# page1.net
KiCad netlist of a schematic drawn in EAGLE
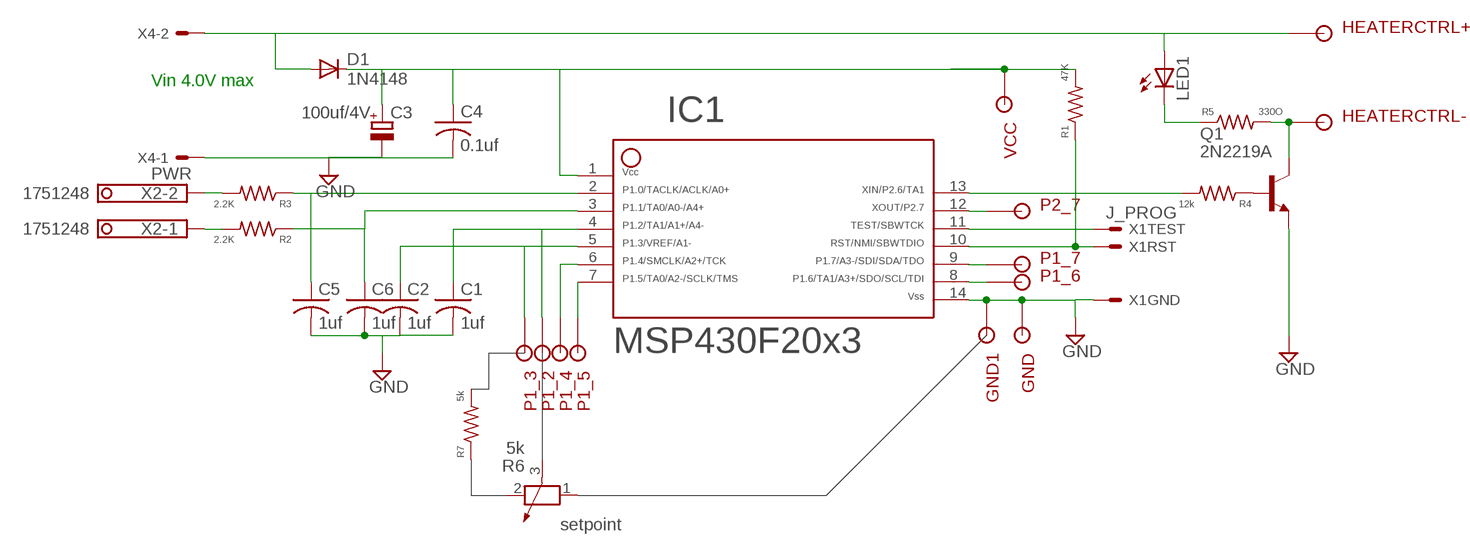
[diagram p0: schematic, sheet 1]

(export (version "E")
  (design (tool "Eeschema 10.0.6"))
  (components
    (comp (ref "C1")
      (value "1uf")
      (footprint "eagle-import:C0805")
      (libsource (lib "eagle-import") (part "C-USC0805"))
    )
    (comp (ref "C2")
      (value "1uf")
      (footprint "eagle-import:C0805")
      (libsource (lib "eagle-import") (part "C-USC0805"))
    )
    (comp (ref "C3")
      (value "100uf/4V")
      (footprint "eagle-import:SMC_B")
      (libsource (lib "eagle-import") (part "CPOL-EUSMCB"))
    )
    (comp (ref "C4")
      (value "0.1uf")
      (footprint "eagle-import:C0805")
      (libsource (lib "eagle-import") (part "C-USC0805"))
    )
    (comp (ref "C5")
      (value "1uf")
      (footprint "eagle-import:C0805")
      (libsource (lib "eagle-import") (part "C-USC0805"))
    )
    (comp (ref "C6")
      (value "1uf")
      (footprint "eagle-import:C0805")
      (libsource (lib "eagle-import") (part "C-USC0805"))
    )
    (comp (ref "D1")
      (value "1N4148")
      (footprint "eagle-import:DIO-35-10")
      (libsource (lib "eagle-import") (part "1N4148"))
    )
    (comp (ref "GND")
      (value "SOLDER_POINTA")
      (footprint "eagle-import:P1-13")
      (libsource (lib "eagle-import") (part "SOLDER_POINTA"))
    )
    (comp (ref "GND1")
      (value "SOLDER_POINTA")
      (footprint "eagle-import:P1-13")
      (libsource (lib "eagle-import") (part "SOLDER_POINTA"))
    )
    (comp (ref "HEATERCTRL+")
      (value "SOLDER_POINTA")
      (footprint "eagle-import:P1-13")
      (libsource (lib "eagle-import") (part "SOLDER_POINTA"))
    )
    (comp (ref "HEATERCTRL-")
      (value "SOLDER_POINTA")
      (footprint "eagle-import:P1-13")
      (libsource (lib "eagle-import") (part "SOLDER_POINTA"))
    )
    (comp (ref "IC1")
      (value "F20X3---N14")
      (footprint "eagle-import:N14")
      (libsource (lib "eagle-import") (part "F20X3---N14"))
    )
    (comp (ref "LED1")
      (value "LED5MM")
      (footprint "eagle-import:LED5MM")
      (libsource (lib "eagle-import") (part "LED5MM"))
    )
    (comp (ref "P1_2")
      (value "SOLDER_POINTA")
      (footprint "eagle-import:P1-13")
      (libsource (lib "eagle-import") (part "SOLDER_POINTA"))
    )
    (comp (ref "P1_3")
      (value "SOLDER_POINTA")
      (footprint "eagle-import:P1-13")
      (libsource (lib "eagle-import") (part "SOLDER_POINTA"))
    )
    (comp (ref "P1_4")
      (value "SOLDER_POINTA")
      (footprint "eagle-import:P1-13")
      (libsource (lib "eagle-import") (part "SOLDER_POINTA"))
    )
    (comp (ref "P1_5")
      (value "SOLDER_POINTA")
      (footprint "eagle-import:P1-13")
      (libsource (lib "eagle-import") (part "SOLDER_POINTA"))
    )
    (comp (ref "P1_6")
      (value "SOLDER_POINTA")
      (footprint "eagle-import:P1-13")
      (libsource (lib "eagle-import") (part "SOLDER_POINTA"))
    )
    (comp (ref "P1_7")
      (value "SOLDER_POINTA")
      (footprint "eagle-import:P1-13")
      (libsource (lib "eagle-import") (part "SOLDER_POINTA"))
    )
    (comp (ref "P2_7")
      (value "SOLDER_POINTA")
      (footprint "eagle-import:P1-13")
      (libsource (lib "eagle-import") (part "SOLDER_POINTA"))
    )
    (comp (ref "Q1")
      (value "2N2219A")
      (footprint "eagle-import:TO92-EBC")
      (libsource (lib "eagle-import") (part "2N2219ATO92_EBC"))
    )
    (comp (ref "R1")
      (value "47K")
      (footprint "eagle-import:M0805")
      (libsource (lib "eagle-import") (part "R-US_M0805"))
    )
    (comp (ref "R2")
      (value "2.2K")
      (footprint "eagle-import:M0805")
      (libsource (lib "eagle-import") (part "R-US_M0805"))
    )
    (comp (ref "R3")
      (value "2.2K")
      (footprint "eagle-import:M0805")
      (libsource (lib "eagle-import") (part "R-US_M0805"))
    )
    (comp (ref "R4")
      (value "12k")
      (footprint "eagle-import:M0805")
      (libsource (lib "eagle-import") (part "R-US_M0805"))
    )
    (comp (ref "R5")
      (value "330O")
      (footprint "eagle-import:0207_15")
      (libsource (lib "eagle-import") (part "R-US_0207/15"))
    )
    (comp (ref "R6")
      (value "5k")
      (footprint "eagle-import:PT-10")
      (libsource (lib "eagle-import") (part "POTENTIOMETER_PT-10"))
    )
    (comp (ref "R7")
      (value "5k")
      (footprint "eagle-import:0207_15")
      (libsource (lib "eagle-import") (part "R-US_0207/15"))
    )
    (comp (ref "VCC")
      (value "SOLDER_POINTA")
      (footprint "eagle-import:P1-13")
      (libsource (lib "eagle-import") (part "SOLDER_POINTA"))
    )
    (comp (ref "X1")
      (value "J_PROG")
      (footprint "eagle-import:MOLEX-3PIN")
      (libsource (lib "eagle-import") (part "J_PROG_MSP430"))
    )
    (comp (ref "X2")
      (value "1751248")
      (footprint "eagle-import:1751248")
      (libsource (lib "eagle-import") (part "1751248"))
    )
    (comp (ref "X4")
      (value "PWR")
      (footprint "eagle-import:22-23-2021")
      (libsource (lib "eagle-import") (part "22-23-2021"))
    )
  )
  (nets
    (net (code "1") (name "GND") (class "Default")
      (node (ref "C1") (pin "2") (pinfunction "2_2") (pintype "passive"))
      (node (ref "C2") (pin "2") (pinfunction "2_2") (pintype "passive"))
      (node (ref "C3") (pin "-") (pinfunction "-_-") (pintype "passive"))
      (node (ref "C4") (pin "2") (pinfunction "2_2") (pintype "passive"))
      (node (ref "C5") (pin "2") (pinfunction "2_2") (pintype "passive"))
      (node (ref "C6") (pin "2") (pinfunction "2_2") (pintype "passive"))
      (node (ref "GND") (pin "1") (pinfunction "P$1_1") (pintype "bidirectional"))
      (node (ref "GND1") (pin "1") (pinfunction "P$1_1") (pintype "bidirectional"))
      (node (ref "IC1") (pin "14") (pinfunction "14_14") (pintype "power_in"))
      (node (ref "Q1") (pin "E") (pinfunction "E_E") (pintype "passive"))
      (node (ref "X1") (pin "3") (pinfunction "S_3") (pintype "passive"))
      (node (ref "X4") (pin "1") (pinfunction "S_1") (pintype "passive"))
    )
    (net (code "2") (name "Net-(C5-Pad1)") (class "Default")
      (node (ref "C5") (pin "1") (pinfunction "1_1") (pintype "passive"))
      (node (ref "IC1") (pin "2") (pinfunction "2_2") (pintype "bidirectional"))
      (node (ref "R3") (pin "1") (pinfunction "1_1") (pintype "passive"))
    )
    (net (code "3") (name "Net-(C6-Pad1)") (class "Default")
      (node (ref "C6") (pin "1") (pinfunction "1_1") (pintype "passive"))
      (node (ref "IC1") (pin "3") (pinfunction "3_3") (pintype "bidirectional"))
      (node (ref "R2") (pin "1") (pinfunction "1_1") (pintype "passive"))
    )
    (net (code "4") (name "Net-(D1-A)") (class "Default")
      (node (ref "D1") (pin "P$2") (pinfunction "A_P$2") (pintype "passive"))
      (node (ref "HEATERCTRL+") (pin "1") (pinfunction "P$1_1") (pintype "bidirectional"))
      (node (ref "LED1") (pin "A") (pinfunction "A_A") (pintype "passive"))
      (node (ref "X4") (pin "2") (pinfunction "S_2") (pintype "passive"))
    )
    (net (code "5") (name "Net-(D1-C)") (class "Default")
      (node (ref "C3") (pin "+") (pinfunction "+_+") (pintype "passive"))
      (node (ref "C4") (pin "1") (pinfunction "1_1") (pintype "passive"))
      (node (ref "D1") (pin "P$1") (pinfunction "C_P$1") (pintype "passive"))
      (node (ref "IC1") (pin "1") (pinfunction "1_1") (pintype "power_in"))
      (node (ref "R1") (pin "2") (pinfunction "2_2") (pintype "passive"))
      (node (ref "VCC") (pin "1") (pinfunction "P$1_1") (pintype "bidirectional"))
    )
    (net (code "6") (name "Net-(HEATERCTRL--P$1)") (class "Default")
      (node (ref "HEATERCTRL-") (pin "1") (pinfunction "P$1_1") (pintype "bidirectional"))
      (node (ref "Q1") (pin "C") (pinfunction "C_C") (pintype "passive"))
      (node (ref "R5") (pin "2") (pinfunction "2_2") (pintype "passive"))
    )
    (net (code "7") (name "Net-(IC1-Pad13)") (class "Default")
      (node (ref "IC1") (pin "13") (pinfunction "13_13") (pintype "bidirectional"))
      (node (ref "R4") (pin "2") (pinfunction "2_2") (pintype "passive"))
    )
    (net (code "8") (name "Net-(LED1-C)") (class "Default")
      (node (ref "LED1") (pin "K") (pinfunction "C_K") (pintype "passive"))
      (node (ref "R5") (pin "1") (pinfunction "1_1") (pintype "passive"))
    )
    (net (code "9") (name "Net-(P1_2-P$1)") (class "Default")
      (node (ref "C1") (pin "1") (pinfunction "1_1") (pintype "passive"))
      (node (ref "IC1") (pin "4") (pinfunction "4_4") (pintype "bidirectional"))
      (node (ref "P1_2") (pin "1") (pinfunction "P$1_1") (pintype "bidirectional"))
    )
    (net (code "10") (name "Net-(P1_3-P$1)") (class "Default")
      (node (ref "C2") (pin "1") (pinfunction "1_1") (pintype "passive"))
      (node (ref "IC1") (pin "5") (pinfunction "5_5") (pintype "bidirectional"))
      (node (ref "P1_3") (pin "1") (pinfunction "P$1_1") (pintype "bidirectional"))
    )
    (net (code "11") (name "Net-(P1_4-P$1)") (class "Default")
      (node (ref "IC1") (pin "6") (pinfunction "6_6") (pintype "bidirectional"))
      (node (ref "P1_4") (pin "1") (pinfunction "P$1_1") (pintype "bidirectional"))
    )
    (net (code "12") (name "Net-(P1_5-P$1)") (class "Default")
      (node (ref "IC1") (pin "7") (pinfunction "7_7") (pintype "bidirectional"))
      (node (ref "P1_5") (pin "1") (pinfunction "P$1_1") (pintype "bidirectional"))
    )
    (net (code "13") (name "Net-(P1_6-P$1)") (class "Default")
      (node (ref "IC1") (pin "8") (pinfunction "8_8") (pintype "bidirectional"))
      (node (ref "P1_6") (pin "1") (pinfunction "P$1_1") (pintype "bidirectional"))
    )
    (net (code "14") (name "Net-(P1_7-P$1)") (class "Default")
      (node (ref "IC1") (pin "9") (pinfunction "9_9") (pintype "bidirectional"))
      (node (ref "P1_7") (pin "1") (pinfunction "P$1_1") (pintype "bidirectional"))
    )
    (net (code "15") (name "Net-(P2_7-P$1)") (class "Default")
      (node (ref "IC1") (pin "12") (pinfunction "12_12") (pintype "bidirectional"))
      (node (ref "P2_7") (pin "1") (pinfunction "P$1_1") (pintype "bidirectional"))
    )
    (net (code "16") (name "Net-(Q1-PadB)") (class "Default")
      (node (ref "Q1") (pin "B") (pinfunction "B_B") (pintype "passive"))
      (node (ref "R4") (pin "1") (pinfunction "1_1") (pintype "passive"))
    )
    (net (code "17") (name "Net-(X1B-S)") (class "Default")
      (node (ref "IC1") (pin "10") (pinfunction "10_10") (pintype "bidirectional"))
      (node (ref "R1") (pin "1") (pinfunction "1_1") (pintype "passive"))
      (node (ref "X1") (pin "2") (pinfunction "S_2") (pintype "passive"))
    )
    (net (code "18") (name "Net-(X1C-S)") (class "Default")
      (node (ref "IC1") (pin "11") (pinfunction "11_11") (pintype "input"))
      (node (ref "X1") (pin "1") (pinfunction "S_1") (pintype "passive"))
    )
    (net (code "19") (name "Net-(X2A-K)") (class "Default")
      (node (ref "R2") (pin "2") (pinfunction "2_2") (pintype "passive"))
      (node (ref "X2") (pin "1") (pinfunction "K_1") (pintype "passive"))
    )
    (net (code "20") (name "Net-(X2B-K)") (class "Default")
      (node (ref "R3") (pin "2") (pinfunction "2_2") (pintype "passive"))
      (node (ref "X2") (pin "2") (pinfunction "K_2") (pintype "passive"))
    )
    (net (code "21") (name "unconnected-(R6-Pad1)") (class "Default")
      (node (ref "R6") (pin "1") (pinfunction "1_1") (pintype "passive"))
    )
    (net (code "22") (name "unconnected-(R6-Pad2)") (class "Default")
      (node (ref "R6") (pin "2") (pinfunction "2_2") (pintype "passive"))
    )
    (net (code "23") (name "unconnected-(R6-Pad3)") (class "Default")
      (node (ref "R6") (pin "3") (pinfunction "3_3") (pintype "passive"))
    )
    (net (code "24") (name "unconnected-(R7-Pad1)") (class "Default")
      (node (ref "R7") (pin "1") (pinfunction "1_1") (pintype "passive"))
    )
    (net (code "25") (name "unconnected-(R7-Pad2)") (class "Default")
      (node (ref "R7") (pin "2") (pinfunction "2_2") (pintype "passive"))
    )
  )
)
